# error.net
KiCad netlist of a schematic drawn in EAGLE
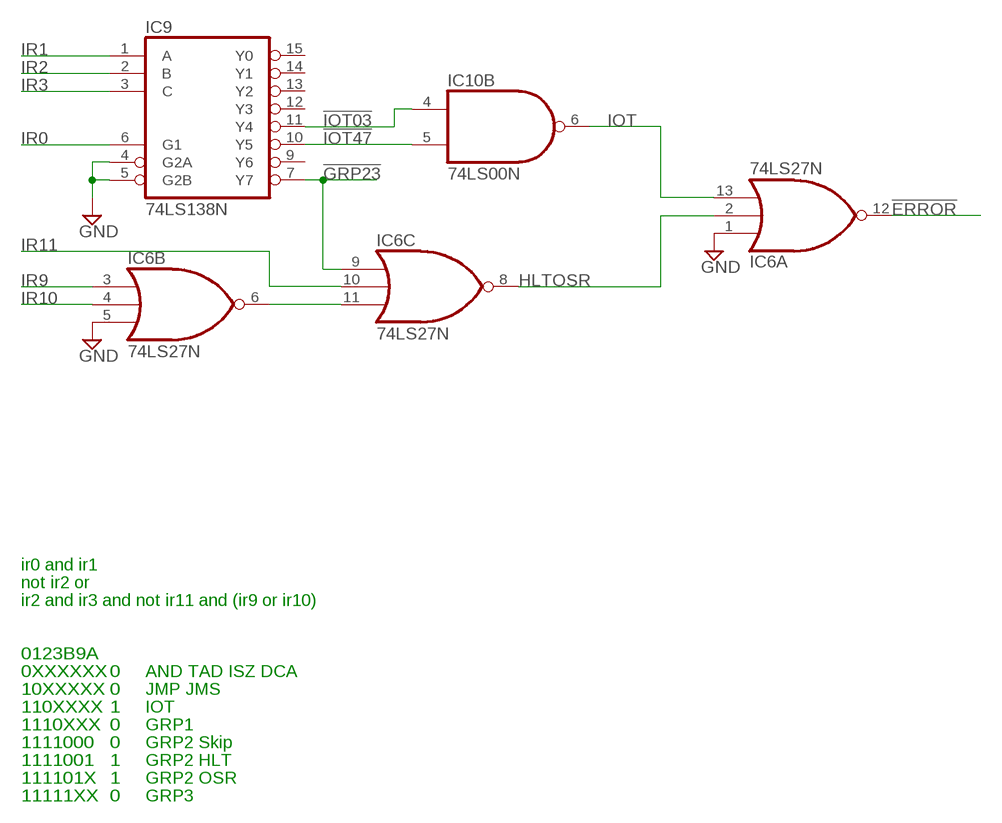
[diagram p0: schematic, sheet 1]

(export (version "E")
  (design (tool "Eeschema 10.0.6"))
  (components
    (comp (ref "IC6")
      (value "74LS27N")
      (footprint "eagle-import:DIL14")
      (libsource (lib "eagle-import") (part "7427NLS"))
    )
    (comp (ref "IC9")
      (value "74LS138N")
      (footprint "eagle-import:DIL16")
      (libsource (lib "eagle-import") (part "74138NLS"))
    )
    (comp (ref "IC10")
      (value "74LS00N")
      (footprint "eagle-import:DIL14")
      (libsource (lib "eagle-import") (part "7400NLS"))
    )
  )
  (nets
    (net (code "1") (name "/HLTOSR") (class "Default")
      (node (ref "IC6") (pin "2") (pinfunction "I1_2") (pintype "input"))
      (node (ref "IC6") (pin "8") (pinfunction "O_8") (pintype "output"))
    )
    (net (code "2") (name "/IOT") (class "Default")
      (node (ref "IC10") (pin "6") (pinfunction "O_6") (pintype "output"))
      (node (ref "IC6") (pin "13") (pinfunction "I2_13") (pintype "input"))
    )
    (net (code "3") (name "/IR0") (class "Default")
      (node (ref "IC9") (pin "6") (pinfunction "G1_6") (pintype "input"))
    )
    (net (code "4") (name "/IR1") (class "Default")
      (node (ref "IC9") (pin "1") (pinfunction "A_1") (pintype "input"))
    )
    (net (code "5") (name "/IR2") (class "Default")
      (node (ref "IC9") (pin "2") (pinfunction "B_2") (pintype "input"))
    )
    (net (code "6") (name "/IR3") (class "Default")
      (node (ref "IC9") (pin "3") (pinfunction "C_3") (pintype "input"))
    )
    (net (code "7") (name "/IR9") (class "Default")
      (node (ref "IC6") (pin "3") (pinfunction "I0_3") (pintype "input"))
    )
    (net (code "8") (name "/IR10") (class "Default")
      (node (ref "IC6") (pin "4") (pinfunction "I1_4") (pintype "input"))
    )
    (net (code "9") (name "/IR11") (class "Default")
      (node (ref "IC6") (pin "10") (pinfunction "I1_10") (pintype "input"))
    )
    (net (code "10") (name "/~{ERROR}") (class "Default")
      (node (ref "IC6") (pin "12") (pinfunction "O_12") (pintype "output"))
    )
    (net (code "11") (name "/~{GRP23}") (class "Default")
      (node (ref "IC6") (pin "9") (pinfunction "I0_9") (pintype "input"))
      (node (ref "IC9") (pin "7") (pinfunction "Y7_7") (pintype "output"))
    )
    (net (code "12") (name "/~{IOT03}") (class "Default")
      (node (ref "IC10") (pin "4") (pinfunction "I0_4") (pintype "input"))
      (node (ref "IC9") (pin "11") (pinfunction "Y4_11") (pintype "output"))
    )
    (net (code "13") (name "/~{IOT47}") (class "Default")
      (node (ref "IC10") (pin "5") (pinfunction "I1_5") (pintype "input"))
      (node (ref "IC9") (pin "10") (pinfunction "Y5_10") (pintype "output"))
    )
    (net (code "14") (name "GND") (class "Default")
      (node (ref "IC6") (pin "1") (pinfunction "I0_1") (pintype "input"))
      (node (ref "IC6") (pin "5") (pinfunction "I2_5") (pintype "input"))
      (node (ref "IC9") (pin "4") (pinfunction "G2A_4") (pintype "input"))
      (node (ref "IC9") (pin "5") (pinfunction "G2B_5") (pintype "input"))
    )
    (net (code "15") (name "Net-(IC6B-O)") (class "Default")
      (node (ref "IC6") (pin "11") (pinfunction "I2_11") (pintype "input"))
      (node (ref "IC6") (pin "6") (pinfunction "O_6") (pintype "output"))
    )
    (net (code "16") (name "unconnected-(IC9A-Y0-Pad15)") (class "Default")
      (node (ref "IC9") (pin "15") (pinfunction "Y0_15") (pintype "output"))
    )
    (net (code "17") (name "unconnected-(IC9A-Y1-Pad14)") (class "Default")
      (node (ref "IC9") (pin "14") (pinfunction "Y1_14") (pintype "output"))
    )
    (net (code "18") (name "unconnected-(IC9A-Y2-Pad13)") (class "Default")
      (node (ref "IC9") (pin "13") (pinfunction "Y2_13") (pintype "output"))
    )
    (net (code "19") (name "unconnected-(IC9A-Y3-Pad12)") (class "Default")
      (node (ref "IC9") (pin "12") (pinfunction "Y3_12") (pintype "output"))
    )
    (net (code "20") (name "unconnected-(IC9A-Y6-Pad9)") (class "Default")
      (node (ref "IC9") (pin "9") (pinfunction "Y6_9") (pintype "output"))
    )
  )
)
